# base_board.net
KiCad netlist of a schematic drawn in Altium Designer
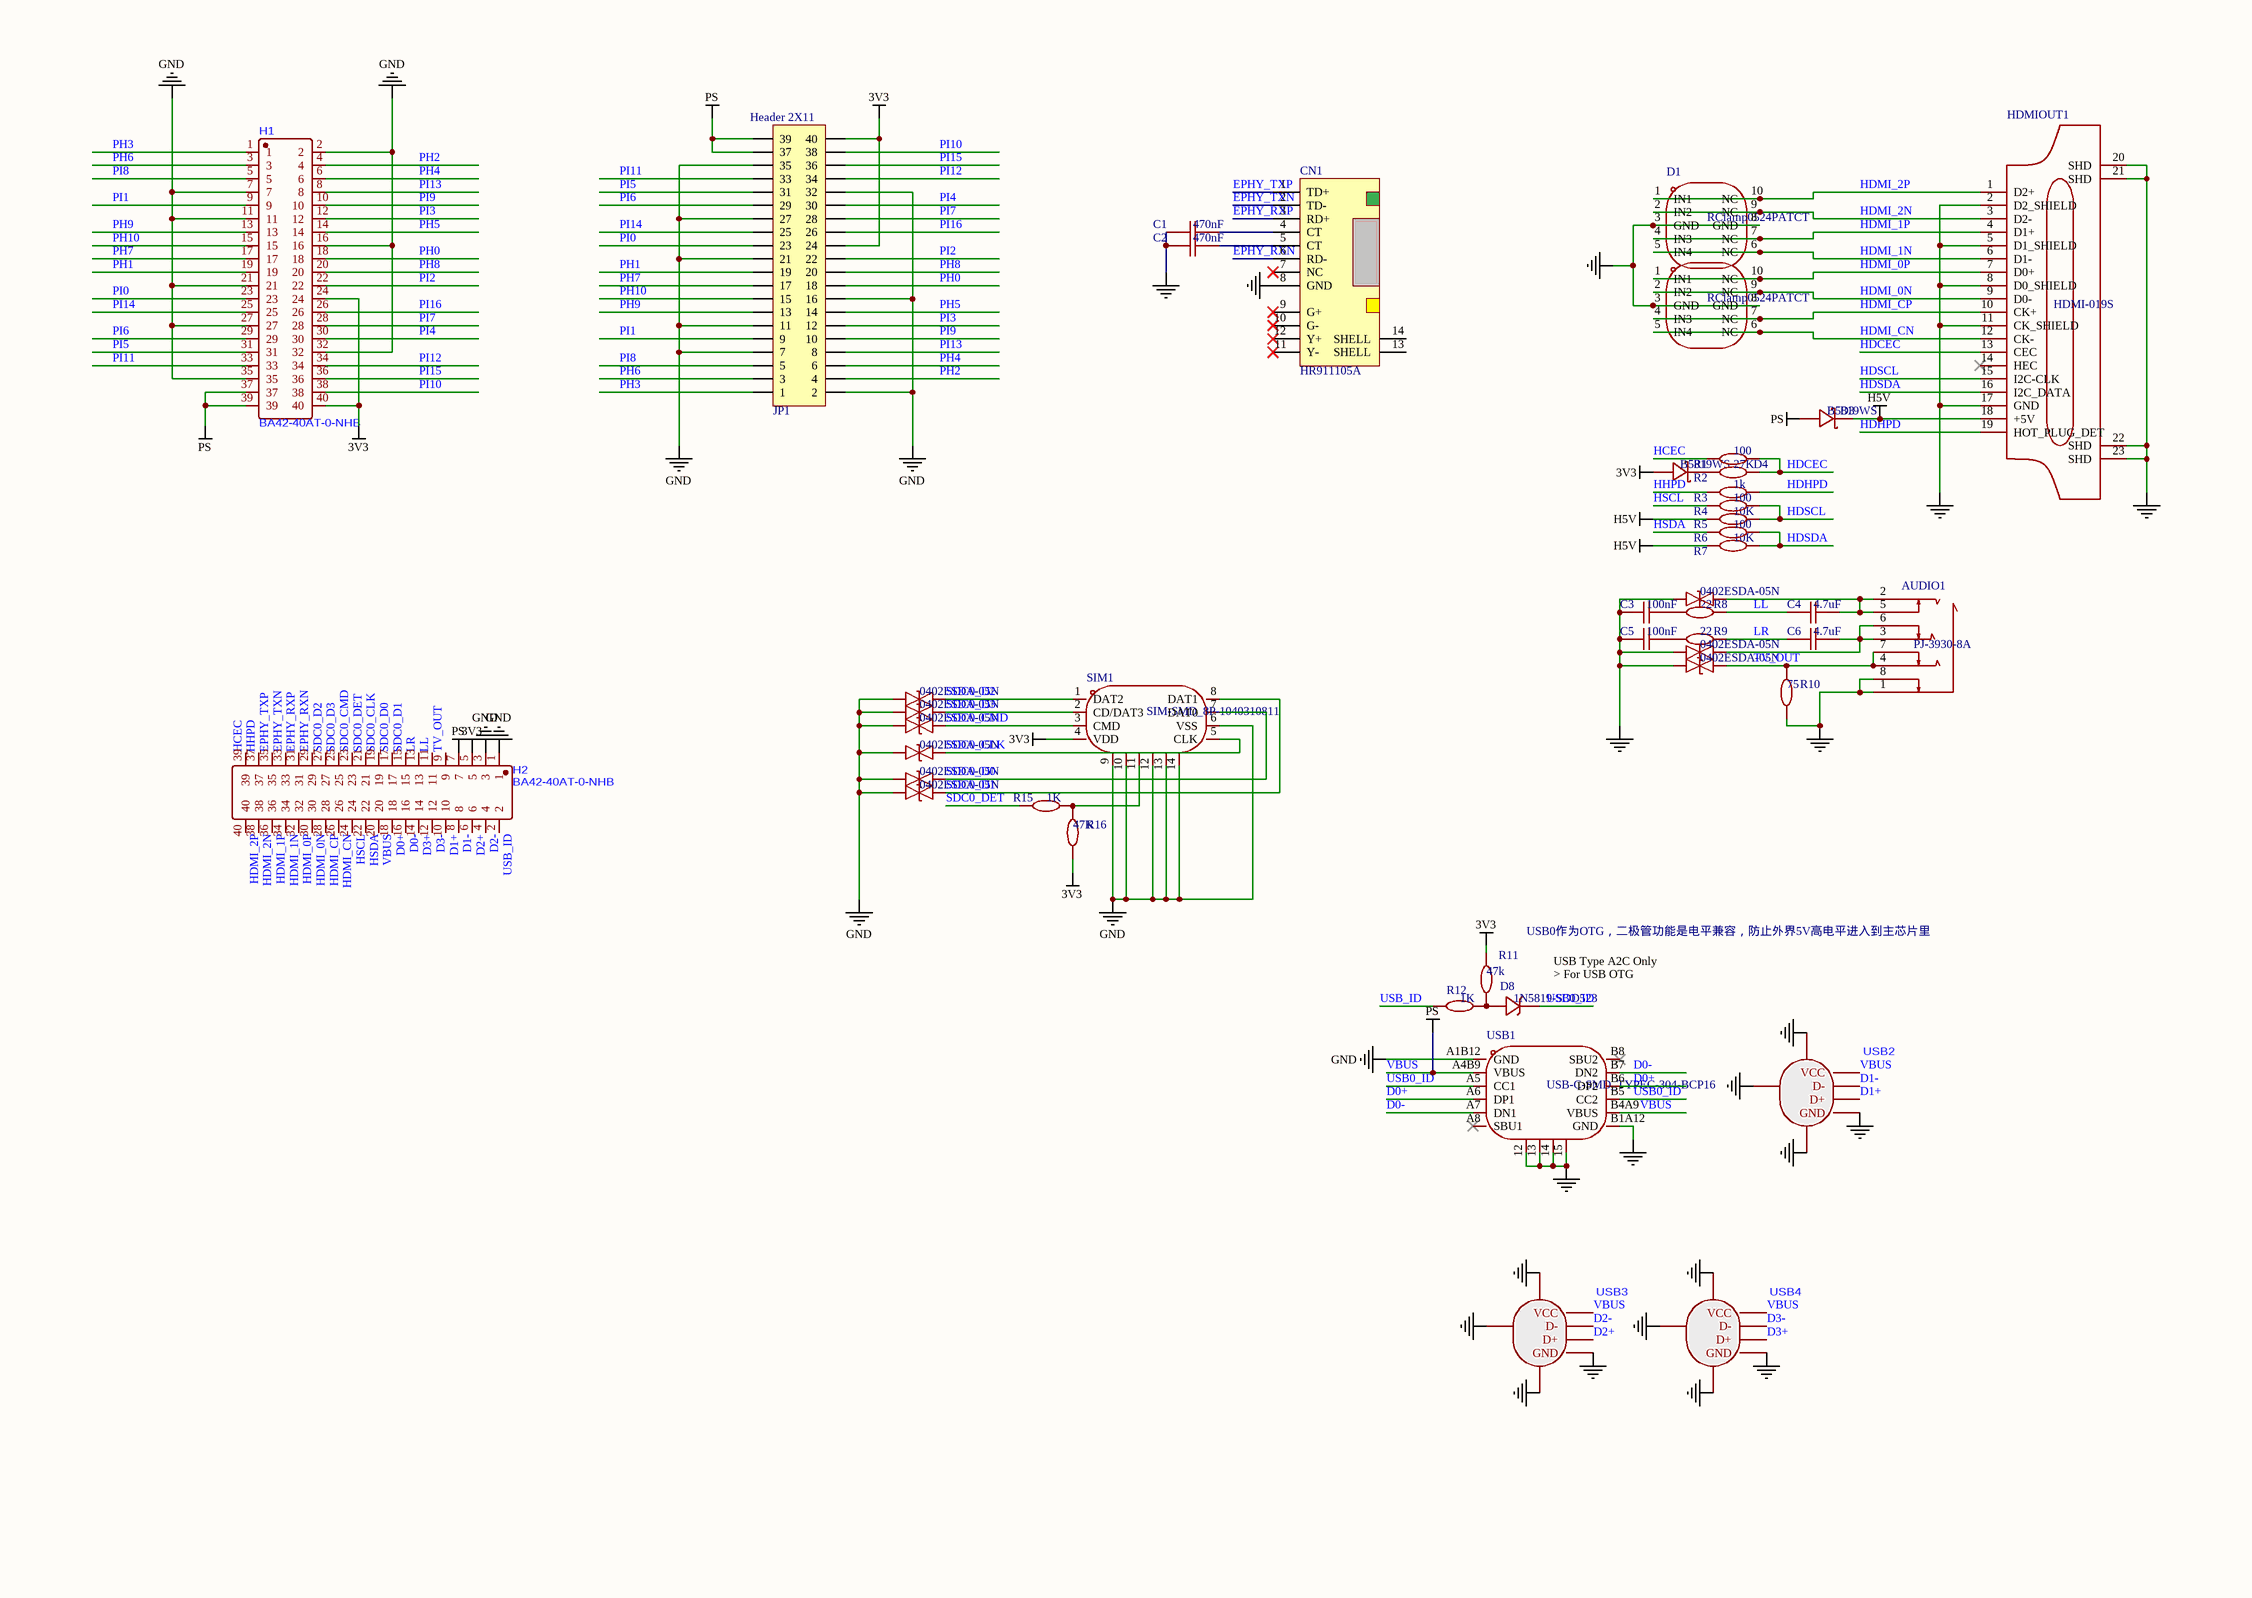
[diagram p0: base_board.schdoc]

(export (version "E")
  (design (tool "Eeschema 10.0.6"))
  (components
    (comp (ref "AUDIO1")
      (value "PJ-3930-8A")
      (footprint "PCB:AUDIO-TH_PJ-3930-8A")
      (libsource (lib "PCB_Project") (part "PJ-3930-8A"))
    )
    (comp (ref "C1")
      (value "470nF")
      (footprint "PCB:C0402")
      (libsource (lib "PCB_Project") (part "CAP_0402"))
    )
    (comp (ref "C2")
      (value "470nF")
      (footprint "PCB:C0402")
      (libsource (lib "PCB_Project") (part "CAP_0402"))
    )
    (comp (ref "C3")
      (value "100nF")
      (footprint "PCB:C0402")
      (libsource (lib "PCB_Project") (part "CAP_0402"))
    )
    (comp (ref "C4")
      (value "4.7uF")
      (footprint "PCB:C0402")
      (libsource (lib "PCB_Project") (part "CAP_0402"))
    )
    (comp (ref "C5")
      (value "100nF")
      (footprint "PCB:C0402")
      (libsource (lib "PCB_Project") (part "CAP_0402"))
    )
    (comp (ref "C6")
      (value "4.7uF")
      (footprint "PCB:C0402")
      (libsource (lib "PCB_Project") (part "CAP_0402"))
    )
    (comp (ref "CN1")
      (value "HR911105A")
      (footprint "PCB:RJ8-HR911105A")
      (description "带灯以太网接口")
      (libsource (lib "PCB_Project") (part "HR911105A"))
    )
    (comp (ref "D1")
      (value "RClamp0524PATCT")
      (footprint "PCB:SLP2510P8_L2.5-W1.0-P0.50-BL")
      (libsource (lib "PCB_Project") (part "RClamp0524PATCT"))
    )
    (comp (ref "D2")
      (value "RClamp0524PATCT")
      (footprint "PCB:SLP2510P8_L2.5-W1.0-P0.50-BL")
      (libsource (lib "PCB_Project") (part "RClamp0524PATCT"))
    )
    (comp (ref "D3")
      (value "B5819WS")
      (footprint "PCB:SOD-323_L1.8-W1.3-LS2.5-NSK")
      (libsource (lib "PCB_Project") (part "B5819WS"))
    )
    (comp (ref "D4")
      (value "B5819WS")
      (footprint "PCB:SOD-323_L1.8-W1.3-LS2.5-NSK")
      (libsource (lib "PCB_Project") (part "B5819WS"))
    )
    (comp (ref "D5")
      (value "0402ESDA-05N")
      (footprint "PCB:D0402")
      (libsource (lib "PCB_Project") (part "0402ESDA-05N"))
    )
    (comp (ref "D6")
      (value "0402ESDA-05N")
      (footprint "PCB:D0402")
      (libsource (lib "PCB_Project") (part "0402ESDA-05N"))
    )
    (comp (ref "D7")
      (value "0402ESDA-05N")
      (footprint "PCB:D0402")
      (libsource (lib "PCB_Project") (part "0402ESDA-05N"))
    )
    (comp (ref "D8")
      (value "1N5819-SOD523")
      (footprint "PCB:SOD-523_L1.2-W0.8-LS1.6-FD")
      (libsource (lib "PCB_Project") (part "1N5819-SOD523"))
    )
    (comp (ref "D9")
      (value "0402ESDA-05N")
      (footprint "PCB:D0402")
      (libsource (lib "PCB_Project") (part "0402ESDA-05N"))
    )
    (comp (ref "D10")
      (value "0402ESDA-05N")
      (footprint "PCB:D0402")
      (libsource (lib "PCB_Project") (part "0402ESDA-05N"))
    )
    (comp (ref "D11")
      (value "0402ESDA-05N")
      (footprint "PCB:D0402")
      (libsource (lib "PCB_Project") (part "0402ESDA-05N"))
    )
    (comp (ref "D12")
      (value "0402ESDA-05N")
      (footprint "PCB:D0402")
      (libsource (lib "PCB_Project") (part "0402ESDA-05N"))
    )
    (comp (ref "D13")
      (value "0402ESDA-05N")
      (footprint "PCB:D0402")
      (libsource (lib "PCB_Project") (part "0402ESDA-05N"))
    )
    (comp (ref "D14")
      (value "0402ESDA-05N")
      (footprint "PCB:D0402")
      (libsource (lib "PCB_Project") (part "0402ESDA-05N"))
    )
    (comp (ref "H1")
      (value "BA42-40AT-0-NHB")
      (footprint "PCB:CONN-SMD_40P-P0.80_10144517-042802LF")
      (libsource (lib "PCB_Project") (part "BA42-40AT-0-NHB"))
    )
    (comp (ref "H2")
      (value "BA42-40AT-0-NHB")
      (footprint "PCB:CONN-SMD_40P-P0.80_10144517-042802LF")
      (libsource (lib "PCB_Project") (part "BA42-40AT-0-NHB"))
    )
    (comp (ref "HDMIOUT1")
      (value "HDMI-019S")
      (footprint "PCB:HDMI-SMD_HDMI-019S")
      (libsource (lib "PCB_Project") (part "HDMI-019S"))
    )
    (comp (ref "JP1")
      (value "Header 2X11")
      (footprint "PCB:HDR2.54-LI-2x20P")
      (description "20*2P接插件")
      (libsource (lib "PCB_Project") (part "Header 20X2"))
    )
    (comp (ref "R1")
      (value "100")
      (footprint "PCB:R0402-NSK_2")
      (libsource (lib "PCB_Project") (part "Res_0402"))
    )
    (comp (ref "R2")
      (value "27K")
      (footprint "PCB:R0402-NSK_2")
      (libsource (lib "PCB_Project") (part "Res_0402"))
    )
    (comp (ref "R3")
      (value "1k")
      (footprint "PCB:R0402-NSK_2")
      (libsource (lib "PCB_Project") (part "Res_0402"))
    )
    (comp (ref "R4")
      (value "100")
      (footprint "PCB:R0402-NSK_2")
      (libsource (lib "PCB_Project") (part "Res_0402"))
    )
    (comp (ref "R5")
      (value "10K")
      (footprint "PCB:R0402-NSK_2")
      (libsource (lib "PCB_Project") (part "Res_0402"))
    )
    (comp (ref "R6")
      (value "100")
      (footprint "PCB:R0402-NSK_2")
      (libsource (lib "PCB_Project") (part "Res_0402"))
    )
    (comp (ref "R7")
      (value "10K")
      (footprint "PCB:R0402-NSK_2")
      (libsource (lib "PCB_Project") (part "Res_0402"))
    )
    (comp (ref "R8")
      (value "22")
      (footprint "PCB:R0402-NSK_2")
      (libsource (lib "PCB_Project") (part "Res_0402"))
    )
    (comp (ref "R9")
      (value "22")
      (footprint "PCB:R0402-NSK_2")
      (libsource (lib "PCB_Project") (part "Res_0402"))
    )
    (comp (ref "R10")
      (value "75")
      (footprint "PCB:R0402-NSK_2")
      (libsource (lib "PCB_Project") (part "Res_0402"))
    )
    (comp (ref "R11")
      (value "47k")
      (footprint "PCB:R0402-NSK_2")
      (libsource (lib "PCB_Project") (part "Res_0402"))
    )
    (comp (ref "R12")
      (value "1K")
      (footprint "PCB:R0402-NSK_2")
      (libsource (lib "PCB_Project") (part "Res_0402"))
    )
    (comp (ref "R15")
      (value "1K")
      (footprint "PCB:R0402-NSK_2")
      (libsource (lib "PCB_Project") (part "Res_0402"))
    )
    (comp (ref "R16")
      (value "47K")
      (footprint "PCB:R0402-NSK_2")
      (libsource (lib "PCB_Project") (part "Res_0402"))
    )
    (comp (ref "SIM1")
      (value "SIM-SMD_8P-1040310811")
      (footprint "PCB:SIM-SMD_8P-1040310811")
      (libsource (lib "PCB_Project") (part "1040310811"))
    )
    (comp (ref "USB1")
      (value "USB-C-SMD_TYPEC-304-BCP16")
      (footprint "PCB:USB-C-SMD_TYPEC-304-BCP16-1")
      (libsource (lib "PCB_Project") (part "TYPEC-304-BCP16"))
    )
    (comp (ref "USB2")
      (value "~")
      (footprint "PCB:USB-A-TH_4P-P1.40-V-F-C39416")
      (libsource (lib "PCB_Project") (part "AFSide of the three straight feet boundless copper14.0PBTWhite plastic90degree"))
    )
    (comp (ref "USB3")
      (value "~")
      (footprint "PCB:USB-A-TH_4P-P1.40-V-F-C39416")
      (libsource (lib "PCB_Project") (part "AFSide of the three straight feet boundless copper14.0PBTWhite plastic90degree"))
    )
    (comp (ref "USB4")
      (value "~")
      (footprint "PCB:USB-A-TH_4P-P1.40-V-F-C39416")
      (libsource (lib "PCB_Project") (part "AFSide of the three straight feet boundless copper14.0PBTWhite plastic90degree"))
    )
  )
  (nets
    (net (code "1") (name "/D0+") (class "Default")
      (node (ref "H2") (pin "18") (pinfunction "18_18") (pintype "passive"))
      (node (ref "USB1") (pin "A6") (pinfunction "DP1_A6") (pintype "passive"))
      (node (ref "USB1") (pin "B6") (pinfunction "DP2_B6") (pintype "passive"))
    )
    (net (code "2") (name "/D0-") (class "Default")
      (node (ref "H2") (pin "16") (pinfunction "16_16") (pintype "passive"))
      (node (ref "USB1") (pin "A7") (pinfunction "DN1_A7") (pintype "passive"))
      (node (ref "USB1") (pin "B7") (pinfunction "DN2_B7") (pintype "passive"))
    )
    (net (code "3") (name "/D1+") (class "Default")
      (node (ref "H2") (pin "10") (pinfunction "10_10") (pintype "passive"))
      (node (ref "USB2") (pin "3") (pinfunction "D+_3") (pintype "passive"))
    )
    (net (code "4") (name "/D1-") (class "Default")
      (node (ref "H2") (pin "8") (pinfunction "8_8") (pintype "passive"))
      (node (ref "USB2") (pin "2") (pinfunction "D-_2") (pintype "passive"))
    )
    (net (code "5") (name "/D2+") (class "Default")
      (node (ref "H2") (pin "6") (pinfunction "6_6") (pintype "passive"))
      (node (ref "USB3") (pin "3") (pinfunction "D+_3") (pintype "passive"))
    )
    (net (code "6") (name "/D2-") (class "Default")
      (node (ref "H2") (pin "4") (pinfunction "4_4") (pintype "passive"))
      (node (ref "USB3") (pin "2") (pinfunction "D-_2") (pintype "passive"))
    )
    (net (code "7") (name "/D3+") (class "Default")
      (node (ref "H2") (pin "14") (pinfunction "14_14") (pintype "passive"))
      (node (ref "USB4") (pin "3") (pinfunction "D+_3") (pintype "passive"))
    )
    (net (code "8") (name "/D3-") (class "Default")
      (node (ref "H2") (pin "12") (pinfunction "12_12") (pintype "passive"))
      (node (ref "USB4") (pin "2") (pinfunction "D-_2") (pintype "passive"))
    )
    (net (code "9") (name "/EPHY_RXN") (class "Default")
      (node (ref "CN1") (pin "6") (pinfunction "RD-_6") (pintype "passive"))
      (node (ref "H2") (pin "29") (pinfunction "29_29") (pintype "passive"))
    )
    (net (code "10") (name "/EPHY_RXP") (class "Default")
      (node (ref "CN1") (pin "3") (pinfunction "RD+_3") (pintype "passive"))
      (node (ref "H2") (pin "31") (pinfunction "31_31") (pintype "passive"))
    )
    (net (code "11") (name "/EPHY_TXN") (class "Default")
      (node (ref "CN1") (pin "2") (pinfunction "TD-_2") (pintype "passive"))
      (node (ref "H2") (pin "33") (pinfunction "33_33") (pintype "passive"))
    )
    (net (code "12") (name "/EPHY_TXP") (class "Default")
      (node (ref "CN1") (pin "1") (pinfunction "TD+_1") (pintype "passive"))
      (node (ref "H2") (pin "35") (pinfunction "35_35") (pintype "passive"))
    )
    (net (code "13") (name "/HCEC") (class "Default")
      (node (ref "H2") (pin "39") (pinfunction "39_39") (pintype "passive"))
      (node (ref "R1") (pin "1") (pinfunction "1_1") (pintype "passive"))
    )
    (net (code "14") (name "/HDCEC") (class "Default")
      (node (ref "HDMIOUT1") (pin "13") (pinfunction "CEC_13") (pintype "passive"))
      (node (ref "R1") (pin "2") (pinfunction "2_2") (pintype "passive"))
      (node (ref "R2") (pin "2") (pinfunction "2_2") (pintype "passive"))
    )
    (net (code "15") (name "/HDHPD") (class "Default")
      (node (ref "HDMIOUT1") (pin "19") (pinfunction "HOT_PLUG_DET_19") (pintype "passive"))
      (node (ref "R3") (pin "2") (pinfunction "2_2") (pintype "passive"))
    )
    (net (code "16") (name "/HDMI_0N") (class "Default")
      (node (ref "D2") (pin "2") (pinfunction "IN2_2") (pintype "passive"))
      (node (ref "D2") (pin "9") (pinfunction "NC_9") (pintype "passive"))
      (node (ref "H2") (pin "30") (pinfunction "30_30") (pintype "passive"))
      (node (ref "HDMIOUT1") (pin "9") (pinfunction "D0-_9") (pintype "passive"))
    )
    (net (code "17") (name "/HDMI_0P") (class "Default")
      (node (ref "D2") (pin "1") (pinfunction "IN1_1") (pintype "passive"))
      (node (ref "D2") (pin "10") (pinfunction "NC_10") (pintype "passive"))
      (node (ref "H2") (pin "32") (pinfunction "32_32") (pintype "passive"))
      (node (ref "HDMIOUT1") (pin "7") (pinfunction "D0+_7") (pintype "passive"))
    )
    (net (code "18") (name "/HDMI_1N") (class "Default")
      (node (ref "D1") (pin "5") (pinfunction "IN4_5") (pintype "passive"))
      (node (ref "D1") (pin "6") (pinfunction "NC_6") (pintype "passive"))
      (node (ref "H2") (pin "34") (pinfunction "34_34") (pintype "passive"))
      (node (ref "HDMIOUT1") (pin "6") (pinfunction "D1-_6") (pintype "passive"))
    )
    (net (code "19") (name "/HDMI_1P") (class "Default")
      (node (ref "D1") (pin "4") (pinfunction "IN3_4") (pintype "passive"))
      (node (ref "D1") (pin "7") (pinfunction "NC_7") (pintype "passive"))
      (node (ref "H2") (pin "36") (pinfunction "36_36") (pintype "passive"))
      (node (ref "HDMIOUT1") (pin "4") (pinfunction "D1+_4") (pintype "passive"))
    )
    (net (code "20") (name "/HDMI_2N") (class "Default")
      (node (ref "D1") (pin "2") (pinfunction "IN2_2") (pintype "passive"))
      (node (ref "D1") (pin "9") (pinfunction "NC_9") (pintype "passive"))
      (node (ref "H2") (pin "38") (pinfunction "38_38") (pintype "passive"))
      (node (ref "HDMIOUT1") (pin "3") (pinfunction "D2-_3") (pintype "passive"))
    )
    (net (code "21") (name "/HDMI_2P") (class "Default")
      (node (ref "D1") (pin "1") (pinfunction "IN1_1") (pintype "passive"))
      (node (ref "D1") (pin "10") (pinfunction "NC_10") (pintype "passive"))
      (node (ref "H2") (pin "40") (pinfunction "40_40") (pintype "passive"))
      (node (ref "HDMIOUT1") (pin "1") (pinfunction "D2+_1") (pintype "passive"))
    )
    (net (code "22") (name "/HDMI_CN") (class "Default")
      (node (ref "D2") (pin "5") (pinfunction "IN4_5") (pintype "passive"))
      (node (ref "D2") (pin "6") (pinfunction "NC_6") (pintype "passive"))
      (node (ref "H2") (pin "26") (pinfunction "26_26") (pintype "passive"))
      (node (ref "HDMIOUT1") (pin "12") (pinfunction "CK-_12") (pintype "passive"))
    )
    (net (code "23") (name "/HDMI_CP") (class "Default")
      (node (ref "D2") (pin "4") (pinfunction "IN3_4") (pintype "passive"))
      (node (ref "D2") (pin "7") (pinfunction "NC_7") (pintype "passive"))
      (node (ref "H2") (pin "28") (pinfunction "28_28") (pintype "passive"))
      (node (ref "HDMIOUT1") (pin "10") (pinfunction "CK+_10") (pintype "passive"))
    )
    (net (code "24") (name "/HDSCL") (class "Default")
      (node (ref "HDMIOUT1") (pin "15") (pinfunction "I2C-CLK_15") (pintype "passive"))
      (node (ref "R4") (pin "2") (pinfunction "2_2") (pintype "passive"))
      (node (ref "R5") (pin "2") (pinfunction "2_2") (pintype "passive"))
    )
    (net (code "25") (name "/HDSDA") (class "Default")
      (node (ref "HDMIOUT1") (pin "16") (pinfunction "I2C_DATA_16") (pintype "passive"))
      (node (ref "R6") (pin "2") (pinfunction "2_2") (pintype "passive"))
      (node (ref "R7") (pin "2") (pinfunction "2_2") (pintype "passive"))
    )
    (net (code "26") (name "/HHPD") (class "Default")
      (node (ref "H2") (pin "37") (pinfunction "37_37") (pintype "passive"))
      (node (ref "R3") (pin "1") (pinfunction "1_1") (pintype "passive"))
    )
    (net (code "27") (name "/HSCL") (class "Default")
      (node (ref "H2") (pin "24") (pinfunction "24_24") (pintype "passive"))
      (node (ref "R4") (pin "1") (pinfunction "1_1") (pintype "passive"))
    )
    (net (code "28") (name "/HSDA") (class "Default")
      (node (ref "H2") (pin "22") (pinfunction "22_22") (pintype "passive"))
      (node (ref "R6") (pin "1") (pinfunction "1_1") (pintype "passive"))
    )
    (net (code "29") (name "/LL") (class "Default")
      (node (ref "C4") (pin "1") (pinfunction "1_1") (pintype "passive"))
      (node (ref "H2") (pin "11") (pinfunction "11_11") (pintype "passive"))
      (node (ref "R8") (pin "2") (pinfunction "2_2") (pintype "passive"))
    )
    (net (code "30") (name "/LR") (class "Default")
      (node (ref "C6") (pin "1") (pinfunction "1_1") (pintype "passive"))
      (node (ref "H2") (pin "13") (pinfunction "13_13") (pintype "passive"))
      (node (ref "R9") (pin "2") (pinfunction "2_2") (pintype "passive"))
    )
    (net (code "31") (name "/PH0") (class "Default")
      (node (ref "H1") (pin "18") (pinfunction "18_18") (pintype "passive"))
      (node (ref "JP1") (pin "18") (pinfunction "18_18") (pintype "passive"))
    )
    (net (code "32") (name "/PH1") (class "Default")
      (node (ref "H1") (pin "19") (pinfunction "19_19") (pintype "passive"))
      (node (ref "JP1") (pin "19") (pinfunction "19_19") (pintype "passive"))
    )
    (net (code "33") (name "/PH2") (class "Default")
      (node (ref "H1") (pin "4") (pinfunction "4_4") (pintype "passive"))
      (node (ref "JP1") (pin "4") (pinfunction "4_4") (pintype "passive"))
    )
    (net (code "34") (name "/PH3") (class "Default")
      (node (ref "H1") (pin "1") (pinfunction "1_1") (pintype "passive"))
      (node (ref "JP1") (pin "1") (pinfunction "1_1") (pintype "passive"))
    )
    (net (code "35") (name "/PH4") (class "Default")
      (node (ref "H1") (pin "6") (pinfunction "6_6") (pintype "passive"))
      (node (ref "JP1") (pin "6") (pinfunction "6_6") (pintype "passive"))
    )
    (net (code "36") (name "/PH5") (class "Default")
      (node (ref "H1") (pin "14") (pinfunction "14_14") (pintype "passive"))
      (node (ref "JP1") (pin "14") (pinfunction "14_14") (pintype "passive"))
    )
    (net (code "37") (name "/PH6") (class "Default")
      (node (ref "H1") (pin "3") (pinfunction "3_3") (pintype "passive"))
      (node (ref "JP1") (pin "3") (pinfunction "3_3") (pintype "passive"))
    )
    (net (code "38") (name "/PH7") (class "Default")
      (node (ref "H1") (pin "17") (pinfunction "17_17") (pintype "passive"))
      (node (ref "JP1") (pin "17") (pinfunction "17_17") (pintype "passive"))
    )
    (net (code "39") (name "/PH8") (class "Default")
      (node (ref "H1") (pin "20") (pinfunction "20_20") (pintype "passive"))
      (node (ref "JP1") (pin "20") (pinfunction "20_20") (pintype "passive"))
    )
    (net (code "40") (name "/PH9") (class "Default")
      (node (ref "H1") (pin "13") (pinfunction "13_13") (pintype "passive"))
      (node (ref "JP1") (pin "13") (pinfunction "13_13") (pintype "passive"))
    )
    (net (code "41") (name "/PH10") (class "Default")
      (node (ref "H1") (pin "15") (pinfunction "15_15") (pintype "passive"))
      (node (ref "JP1") (pin "15") (pinfunction "15_15") (pintype "passive"))
    )
    (net (code "42") (name "/PI0") (class "Default")
      (node (ref "H1") (pin "23") (pinfunction "23_23") (pintype "passive"))
      (node (ref "JP1") (pin "23") (pinfunction "23_23") (pintype "passive"))
    )
    (net (code "43") (name "/PI1") (class "Default")
      (node (ref "H1") (pin "9") (pinfunction "9_9") (pintype "passive"))
      (node (ref "JP1") (pin "9") (pinfunction "9_9") (pintype "passive"))
    )
    (net (code "44") (name "/PI2") (class "Default")
      (node (ref "H1") (pin "22") (pinfunction "22_22") (pintype "passive"))
      (node (ref "JP1") (pin "22") (pinfunction "22_22") (pintype "passive"))
    )
    (net (code "45") (name "/PI3") (class "Default")
      (node (ref "H1") (pin "12") (pinfunction "12_12") (pintype "passive"))
      (node (ref "JP1") (pin "12") (pinfunction "12_12") (pintype "passive"))
    )
    (net (code "46") (name "/PI4") (class "Default")
      (node (ref "H1") (pin "30") (pinfunction "30_30") (pintype "passive"))
      (node (ref "JP1") (pin "30") (pinfunction "30_30") (pintype "passive"))
    )
    (net (code "47") (name "/PI5") (class "Default")
      (node (ref "H1") (pin "31") (pinfunction "31_31") (pintype "passive"))
      (node (ref "JP1") (pin "31") (pinfunction "31_31") (pintype "passive"))
    )
    (net (code "48") (name "/PI6") (class "Default")
      (node (ref "H1") (pin "29") (pinfunction "29_29") (pintype "passive"))
      (node (ref "JP1") (pin "29") (pinfunction "29_29") (pintype "passive"))
    )
    (net (code "49") (name "/PI7") (class "Default")
      (node (ref "H1") (pin "28") (pinfunction "28_28") (pintype "passive"))
      (node (ref "JP1") (pin "28") (pinfunction "28_28") (pintype "passive"))
    )
    (net (code "50") (name "/PI8") (class "Default")
      (node (ref "H1") (pin "5") (pinfunction "5_5") (pintype "passive"))
      (node (ref "JP1") (pin "5") (pinfunction "5_5") (pintype "passive"))
    )
    (net (code "51") (name "/PI9") (class "Default")
      (node (ref "H1") (pin "10") (pinfunction "10_10") (pintype "passive"))
      (node (ref "JP1") (pin "10") (pinfunction "10_10") (pintype "passive"))
    )
    (net (code "52") (name "/PI10") (class "Default")
      (node (ref "H1") (pin "38") (pinfunction "38_38") (pintype "passive"))
      (node (ref "JP1") (pin "38") (pinfunction "38_38") (pintype "passive"))
    )
    (net (code "53") (name "/PI11") (class "Default")
      (node (ref "H1") (pin "33") (pinfunction "33_33") (pintype "passive"))
      (node (ref "JP1") (pin "33") (pinfunction "33_33") (pintype "passive"))
    )
    (net (code "54") (name "/PI12") (class "Default")
      (node (ref "H1") (pin "34") (pinfunction "34_34") (pintype "passive"))
      (node (ref "JP1") (pin "34") (pinfunction "34_34") (pintype "passive"))
    )
    (net (code "55") (name "/PI13") (class "Default")
      (node (ref "H1") (pin "8") (pinfunction "8_8") (pintype "passive"))
      (node (ref "JP1") (pin "8") (pinfunction "8_8") (pintype "passive"))
    )
    (net (code "56") (name "/PI14") (class "Default")
      (node (ref "H1") (pin "25") (pinfunction "25_25") (pintype "passive"))
      (node (ref "JP1") (pin "25") (pinfunction "25_25") (pintype "passive"))
    )
    (net (code "57") (name "/PI15") (class "Default")
      (node (ref "H1") (pin "36") (pinfunction "36_36") (pintype "passive"))
      (node (ref "JP1") (pin "36") (pinfunction "36_36") (pintype "passive"))
    )
    (net (code "58") (name "/PI16") (class "Default")
      (node (ref "H1") (pin "26") (pinfunction "26_26") (pintype "passive"))
      (node (ref "JP1") (pin "26") (pinfunction "26_26") (pintype "passive"))
    )
    (net (code "59") (name "/SDC0_CLK") (class "Default")
      (node (ref "D12") (pin "2") (pinfunction "2_2") (pintype "passive"))
      (node (ref "H2") (pin "19") (pinfunction "19_19") (pintype "passive"))
      (node (ref "SIM1") (pin "5") (pinfunction "CLK_5") (pintype "passive"))
    )
    (net (code "60") (name "/SDC0_CMD") (class "Default")
      (node (ref "D11") (pin "2") (pinfunction "2_2") (pintype "passive"))
      (node (ref "H2") (pin "23") (pinfunction "23_23") (pintype "passive"))
      (node (ref "SIM1") (pin "3") (pinfunction "CMD_3") (pintype "passive"))
    )
    (net (code "61") (name "/SDC0_D0") (class "Default")
      (node (ref "D13") (pin "2") (pinfunction "2_2") (pintype "passive"))
      (node (ref "H2") (pin "17") (pinfunction "17_17") (pintype "passive"))
      (node (ref "SIM1") (pin "7") (pinfunction "DAT0_7") (pintype "passive"))
    )
    (net (code "62") (name "/SDC0_D1") (class "Default")
      (node (ref "D14") (pin "2") (pinfunction "2_2") (pintype "passive"))
      (node (ref "H2") (pin "15") (pinfunction "15_15") (pintype "passive"))
      (node (ref "SIM1") (pin "8") (pinfunction "DAT1_8") (pintype "passive"))
    )
    (net (code "63") (name "/SDC0_D2") (class "Default")
      (node (ref "D9") (pin "2") (pinfunction "2_2") (pintype "passive"))
      (node (ref "H2") (pin "27") (pinfunction "27_27") (pintype "passive"))
      (node (ref "SIM1") (pin "1") (pinfunction "DAT2_1") (pintype "passive"))
    )
    (net (code "64") (name "/SDC0_D3") (class "Default")
      (node (ref "D10") (pin "2") (pinfunction "2_2") (pintype "passive"))
      (node (ref "H2") (pin "25") (pinfunction "25_25") (pintype "passive"))
      (node (ref "SIM1") (pin "2") (pinfunction "CD/DAT3_2") (pintype "passive"))
    )
    (net (code "65") (name "/SDC0_DET") (class "Default")
      (node (ref "H2") (pin "21") (pinfunction "21_21") (pintype "passive"))
      (node (ref "R15") (pin "1") (pinfunction "1_1") (pintype "passive"))
    )
    (net (code "66") (name "/TV_OUT") (class "Default")
      (node (ref "AUDIO1") (pin "4") (pinfunction "4_4") (pintype "passive"))
      (node (ref "AUDIO1") (pin "7") (pinfunction "7_7") (pintype "passive"))
      (node (ref "D7") (pin "2") (pinfunction "2_2") (pintype "passive"))
      (node (ref "H2") (pin "9") (pinfunction "9_9") (pintype "passive"))
      (node (ref "R10") (pin "2") (pinfunction "2_2") (pintype "passive"))
    )
    (net (code "67") (name "/USB0_ID") (class "Default")
      (node (ref "D8") (pin "2") (pinfunction "K_2") (pintype "passive"))
      (node (ref "USB1") (pin "A5") (pinfunction "CC1_A5") (pintype "passive"))
      (node (ref "USB1") (pin "B5") (pinfunction "CC2_B5") (pintype "passive"))
    )
    (net (code "68") (name "/USB_ID") (class "Default")
      (node (ref "H2") (pin "2") (pinfunction "2_2") (pintype "passive"))
      (node (ref "R12") (pin "1") (pinfunction "1_1") (pintype "passive"))
    )
    (net (code "69") (name "3V3") (class "Default")
      (node (ref "D4") (pin "2") (pinfunction "A_2") (pintype "passive"))
      (node (ref "H1") (pin "24") (pinfunction "24_24") (pintype "passive"))
      (node (ref "H1") (pin "40") (pinfunction "40_40") (pintype "passive"))
      (node (ref "H2") (pin "5") (pinfunction "5_5") (pintype "passive"))
      (node (ref "JP1") (pin "24") (pinfunction "24_24") (pintype "passive"))
      (node (ref "JP1") (pin "40") (pinfunction "40_40") (pintype "passive"))
      (node (ref "R11") (pin "2") (pinfunction "2_2") (pintype "passive"))
      (node (ref "R16") (pin "1") (pinfunction "1_1") (pintype "passive"))
      (node (ref "SIM1") (pin "4") (pinfunction "VDD_4") (pintype "passive"))
    )
    (net (code "70") (name "GND") (class "Default")
      (node (ref "AUDIO1") (pin "1") (pinfunction "1_1") (pintype "passive"))
      (node (ref "AUDIO1") (pin "8") (pinfunction "8_8") (pintype "passive"))
      (node (ref "C1") (pin "1") (pinfunction "1_1") (pintype "passive"))
      (node (ref "C2") (pin "1") (pinfunction "1_1") (pintype "passive"))
      (node (ref "C3") (pin "1") (pinfunction "1_1") (pintype "passive"))
      (node (ref "C5") (pin "1") (pinfunction "1_1") (pintype "passive"))
      (node (ref "CN1") (pin "8") (pinfunction "GND_8") (pintype "passive"))
      (node (ref "D1") (pin "3") (pinfunction "GND_3") (pintype "passive"))
      (node (ref "D1") (pin "8") (pinfunction "GND_8") (pintype "passive"))
      (node (ref "D10") (pin "1") (pinfunction "1_1") (pintype "passive"))
      (node (ref "D11") (pin "1") (pinfunction "1_1") (pintype "passive"))
      (node (ref "D12") (pin "1") (pinfunction "1_1") (pintype "passive"))
      (node (ref "D13") (pin "1") (pinfunction "1_1") (pintype "passive"))
      (node (ref "D14") (pin "1") (pinfunction "1_1") (pintype "passive"))
      (node (ref "D2") (pin "3") (pinfunction "GND_3") (pintype "passive"))
      (node (ref "D2") (pin "8") (pinfunction "GND_8") (pintype "passive"))
      (node (ref "D5") (pin "1") (pinfunction "1_1") (pintype "passive"))
      (node (ref "D6") (pin "1") (pinfunction "1_1") (pintype "passive"))
      (node (ref "D7") (pin "1") (pinfunction "1_1") (pintype "passive"))
      (node (ref "D9") (pin "1") (pinfunction "1_1") (pintype "passive"))
      (node (ref "H1") (pin "11") (pinfunction "11_11") (pintype "passive"))
      (node (ref "H1") (pin "16") (pinfunction "16_16") (pintype "passive"))
      (node (ref "H1") (pin "2") (pinfunction "2_2") (pintype "passive"))
      (node (ref "H1") (pin "21") (pinfunction "21_21") (pintype "passive"))
      (node (ref "H1") (pin "27") (pinfunction "27_27") (pintype "passive"))
      (node (ref "H1") (pin "32") (pinfunction "32_32") (pintype "passive"))
      (node (ref "H1") (pin "35") (pinfunction "35_35") (pintype "passive"))
      (node (ref "H1") (pin "7") (pinfunction "7_7") (pintype "passive"))
      (node (ref "H2") (pin "1") (pinfunction "1_1") (pintype "passive"))
      (node (ref "H2") (pin "3") (pinfunction "3_3") (pintype "passive"))
      (node (ref "HDMIOUT1") (pin "11") (pinfunction "CK_SHIELD_11") (pintype "passive"))
      (node (ref "HDMIOUT1") (pin "17") (pinfunction "GND_17") (pintype "passive"))
      (node (ref "HDMIOUT1") (pin "2") (pinfunction "D2_SHIELD_2") (pintype "passive"))
      (node (ref "HDMIOUT1") (pin "20") (pinfunction "SHD_20") (pintype "passive"))
      (node (ref "HDMIOUT1") (pin "21") (pinfunction "SHD_21") (pintype "passive"))
      (node (ref "HDMIOUT1") (pin "22") (pinfunction "SHD_22") (pintype "passive"))
      (node (ref "HDMIOUT1") (pin "23") (pinfunction "SHD_23") (pintype "passive"))
      (node (ref "HDMIOUT1") (pin "5") (pinfunction "D1_SHIELD_5") (pintype "passive"))
      (node (ref "HDMIOUT1") (pin "8") (pinfunction "D0_SHIELD_8") (pintype "passive"))
      (node (ref "JP1") (pin "11") (pinfunction "11_11") (pintype "passive"))
      (node (ref "JP1") (pin "16") (pinfunction "16_16") (pintype "passive"))
      (node (ref "JP1") (pin "2") (pinfunction "2_2") (pintype "passive"))
      (node (ref "JP1") (pin "21") (pinfunction "21_21") (pintype "passive"))
      (node (ref "JP1") (pin "27") (pinfunction "27_27") (pintype "passive"))
      (node (ref "JP1") (pin "32") (pinfunction "32_32") (pintype "passive"))
      (node (ref "JP1") (pin "35") (pinfunction "35_35") (pintype "passive"))
      (node (ref "JP1") (pin "7") (pinfunction "7_7") (pintype "passive"))
      (node (ref "R10") (pin "1") (pinfunction "1_1") (pintype "passive"))
      (node (ref "SIM1") (pin "10") (pinfunction "10_10") (pintype "passive"))
      (node (ref "SIM1") (pin "12") (pinfunction "12_12") (pintype "passive"))
      (node (ref "SIM1") (pin "13") (pinfunction "13_13") (pintype "passive"))
      (node (ref "SIM1") (pin "14") (pinfunction "14_14") (pintype "passive"))
      (node (ref "SIM1") (pin "6") (pinfunction "VSS_6") (pintype "passive"))
      (node (ref "SIM1") (pin "9") (pinfunction "9_9") (pintype "passive"))
      (node (ref "USB1") (pin "12") (pinfunction "1_12") (pintype "passive"))
      (node (ref "USB1") (pin "13") (pinfunction "2_13") (pintype "passive"))
      (node (ref "USB1") (pin "14") (pinfunction "3_14") (pintype "passive"))
      (node (ref "USB1") (pin "15") (pinfunction "4_15") (pintype "passive"))
      (node (ref "USB1") (pin "A1B12") (pinfunction "GND_A1B12") (pintype "passive"))
      (node (ref "USB1") (pin "B1A12") (pinfunction "GND_B1A12") (pintype "passive"))
      (node (ref "USB2") (pin "4") (pinfunction "GND_4") (pintype "passive"))
      (node (ref "USB2") (pin "5") (pinfunction "5_5") (pintype "passive"))
      (node (ref "USB2") (pin "6") (pinfunction "6_6") (pintype "passive"))
      (node (ref "USB2") (pin "7") (pinfunction "7_7") (pintype "passive"))
      (node (ref "USB3") (pin "4") (pinfunction "GND_4") (pintype "passive"))
      (node (ref "USB3") (pin "5") (pinfunction "5_5") (pintype "passive"))
      (node (ref "USB3") (pin "6") (pinfunction "6_6") (pintype "passive"))
      (node (ref "USB3") (pin "7") (pinfunction "7_7") (pintype "passive"))
      (node (ref "USB4") (pin "4") (pinfunction "GND_4") (pintype "passive"))
      (node (ref "USB4") (pin "5") (pinfunction "5_5") (pintype "passive"))
      (node (ref "USB4") (pin "6") (pinfunction "6_6") (pintype "passive"))
      (node (ref "USB4") (pin "7") (pinfunction "7_7") (pintype "passive"))
    )
    (net (code "71") (name "H5V") (class "Default")
      (node (ref "D3") (pin "1") (pinfunction "K_1") (pintype "passive"))
      (node (ref "HDMIOUT1") (pin "18") (pinfunction "+5V_18") (pintype "passive"))
      (node (ref "R5") (pin "1") (pinfunction "1_1") (pintype "passive"))
      (node (ref "R7") (pin "1") (pinfunction "1_1") (pintype "passive"))
    )
    (net (code "72") (name "Net-(AUDIO1-Pad2)") (class "Default")
      (node (ref "AUDIO1") (pin "2") (pinfunction "2_2") (pintype "passive"))
      (node (ref "AUDIO1") (pin "5") (pinfunction "5_5") (pintype "passive"))
      (node (ref "C4") (pin "2") (pinfunction "2_2") (pintype "passive"))
      (node (ref "D5") (pin "2") (pinfunction "2_2") (pintype "passive"))
    )
    (net (code "73") (name "Net-(AUDIO1-Pad3)") (class "Default")
      (node (ref "AUDIO1") (pin "3") (pinfunction "3_3") (pintype "passive"))
      (node (ref "AUDIO1") (pin "6") (pinfunction "6_6") (pintype "passive"))
      (node (ref "C6") (pin "2") (pinfunction "2_2") (pintype "passive"))
      (node (ref "D6") (pin "2") (pinfunction "2_2") (pintype "passive"))
    )
    (net (code "74") (name "Net-(C1-Pad2)") (class "Default")
      (node (ref "C1") (pin "2") (pinfunction "2_2") (pintype "passive"))
      (node (ref "CN1") (pin "4") (pinfunction "CT_4") (pintype "passive"))
    )
    (net (code "75") (name "Net-(C2-Pad2)") (class "Default")
      (node (ref "C2") (pin "2") (pinfunction "2_2") (pintype "passive"))
      (node (ref "CN1") (pin "5") (pinfunction "CT_5") (pintype "passive"))
    )
    (net (code "76") (name "Net-(C3-Pad2)") (class "Default")
      (node (ref "C3") (pin "2") (pinfunction "2_2") (pintype "passive"))
      (node (ref "R8") (pin "1") (pinfunction "1_1") (pintype "passive"))
    )
    (net (code "77") (name "Net-(C5-Pad2)") (class "Default")
      (node (ref "C5") (pin "2") (pinfunction "2_2") (pintype "passive"))
      (node (ref "R9") (pin "1") (pinfunction "1_1") (pintype "passive"))
    )
    (net (code "78") (name "Net-(D4-K)") (class "Default")
      (node (ref "D4") (pin "1") (pinfunction "K_1") (pintype "passive"))
      (node (ref "R2") (pin "1") (pinfunction "1_1") (pintype "passive"))
    )
    (net (code "79") (name "Net-(D8-A)") (class "Default")
      (node (ref "D8") (pin "1") (pinfunction "A_1") (pintype "passive"))
      (node (ref "R11") (pin "1") (pinfunction "1_1") (pintype "passive"))
      (node (ref "R12") (pin "2") (pinfunction "2_2") (pintype "passive"))
    )
    (net (code "80") (name "Net-(R15-Pad2)") (class "Default")
      (node (ref "R15") (pin "2") (pinfunction "2_2") (pintype "passive"))
      (node (ref "R16") (pin "2") (pinfunction "2_2") (pintype "passive"))
      (node (ref "SIM1") (pin "11") (pinfunction "11_11") (pintype "passive"))
    )
    (net (code "81") (name "PS") (class "Default")
      (node (ref "D3") (pin "2") (pinfunction "A_2") (pintype "passive"))
      (node (ref "H1") (pin "37") (pinfunction "37_37") (pintype "passive"))
      (node (ref "H1") (pin "39") (pinfunction "39_39") (pintype "passive"))
      (node (ref "H2") (pin "20") (pinfunction "20_20") (pintype "passive"))
      (node (ref "H2") (pin "7") (pinfunction "7_7") (pintype "passive"))
      (node (ref "JP1") (pin "37") (pinfunction "37_37") (pintype "passive"))
      (node (ref "JP1") (pin "39") (pinfunction "39_39") (pintype "passive"))
      (node (ref "USB1") (pin "A4B9") (pinfunction "VBUS_A4B9") (pintype "passive"))
      (node (ref "USB1") (pin "B4A9") (pinfunction "VBUS_B4A9") (pintype "passive"))
      (node (ref "USB2") (pin "1") (pinfunction "VCC_1") (pintype "passive"))
      (node (ref "USB3") (pin "1") (pinfunction "VCC_1") (pintype "passive"))
      (node (ref "USB4") (pin "1") (pinfunction "VCC_1") (pintype "passive"))
    )
    (net (code "82") (name "unconnected-(CN1-G+-Pad9)") (class "Default")
      (node (ref "CN1") (pin "9") (pinfunction "G+_9") (pintype "passive+no_connect"))
    )
    (net (code "83") (name "unconnected-(CN1-G--Pad10)") (class "Default")
      (node (ref "CN1") (pin "10") (pinfunction "G-_10") (pintype "passive+no_connect"))
    )
    (net (code "84") (name "unconnected-(CN1-NC-Pad7)") (class "Default")
      (node (ref "CN1") (pin "7") (pinfunction "NC_7") (pintype "passive+no_connect"))
    )
    (net (code "85") (name "unconnected-(CN1-SHELL-Pad13)") (class "Default")
      (node (ref "CN1") (pin "13") (pinfunction "SHELL_13") (pintype "passive"))
    )
    (net (code "86") (name "unconnected-(CN1-SHELL-Pad14)") (class "Default")
      (node (ref "CN1") (pin "14") (pinfunction "SHELL_14") (pintype "passive"))
    )
    (net (code "87") (name "unconnected-(CN1-Y+-Pad12)") (class "Default")
      (node (ref "CN1") (pin "12") (pinfunction "Y+_12") (pintype "passive+no_connect"))
    )
    (net (code "88") (name "unconnected-(CN1-Y--Pad11)") (class "Default")
      (node (ref "CN1") (pin "11") (pinfunction "Y-_11") (pintype "passive+no_connect"))
    )
    (net (code "89") (name "unconnected-(HDMIOUT1-HEC-Pad14)") (class "Default")
      (node (ref "HDMIOUT1") (pin "14") (pinfunction "HEC_14") (pintype "passive+no_connect"))
    )
    (net (code "90") (name "unconnected-(USB1-SBU1-PadA8)") (class "Default")
      (node (ref "USB1") (pin "A8") (pinfunction "SBU1_A8") (pintype "passive+no_connect"))
    )
    (net (code "91") (name "unconnected-(USB1-SBU2-PadB8)") (class "Default")
      (node (ref "USB1") (pin "B8") (pinfunction "SBU2_B8") (pintype "passive+no_connect"))
    )
  )
)
